# USB_C_Vertical_Breakout-PTH.net
KiCad netlist of a schematic drawn in EAGLE
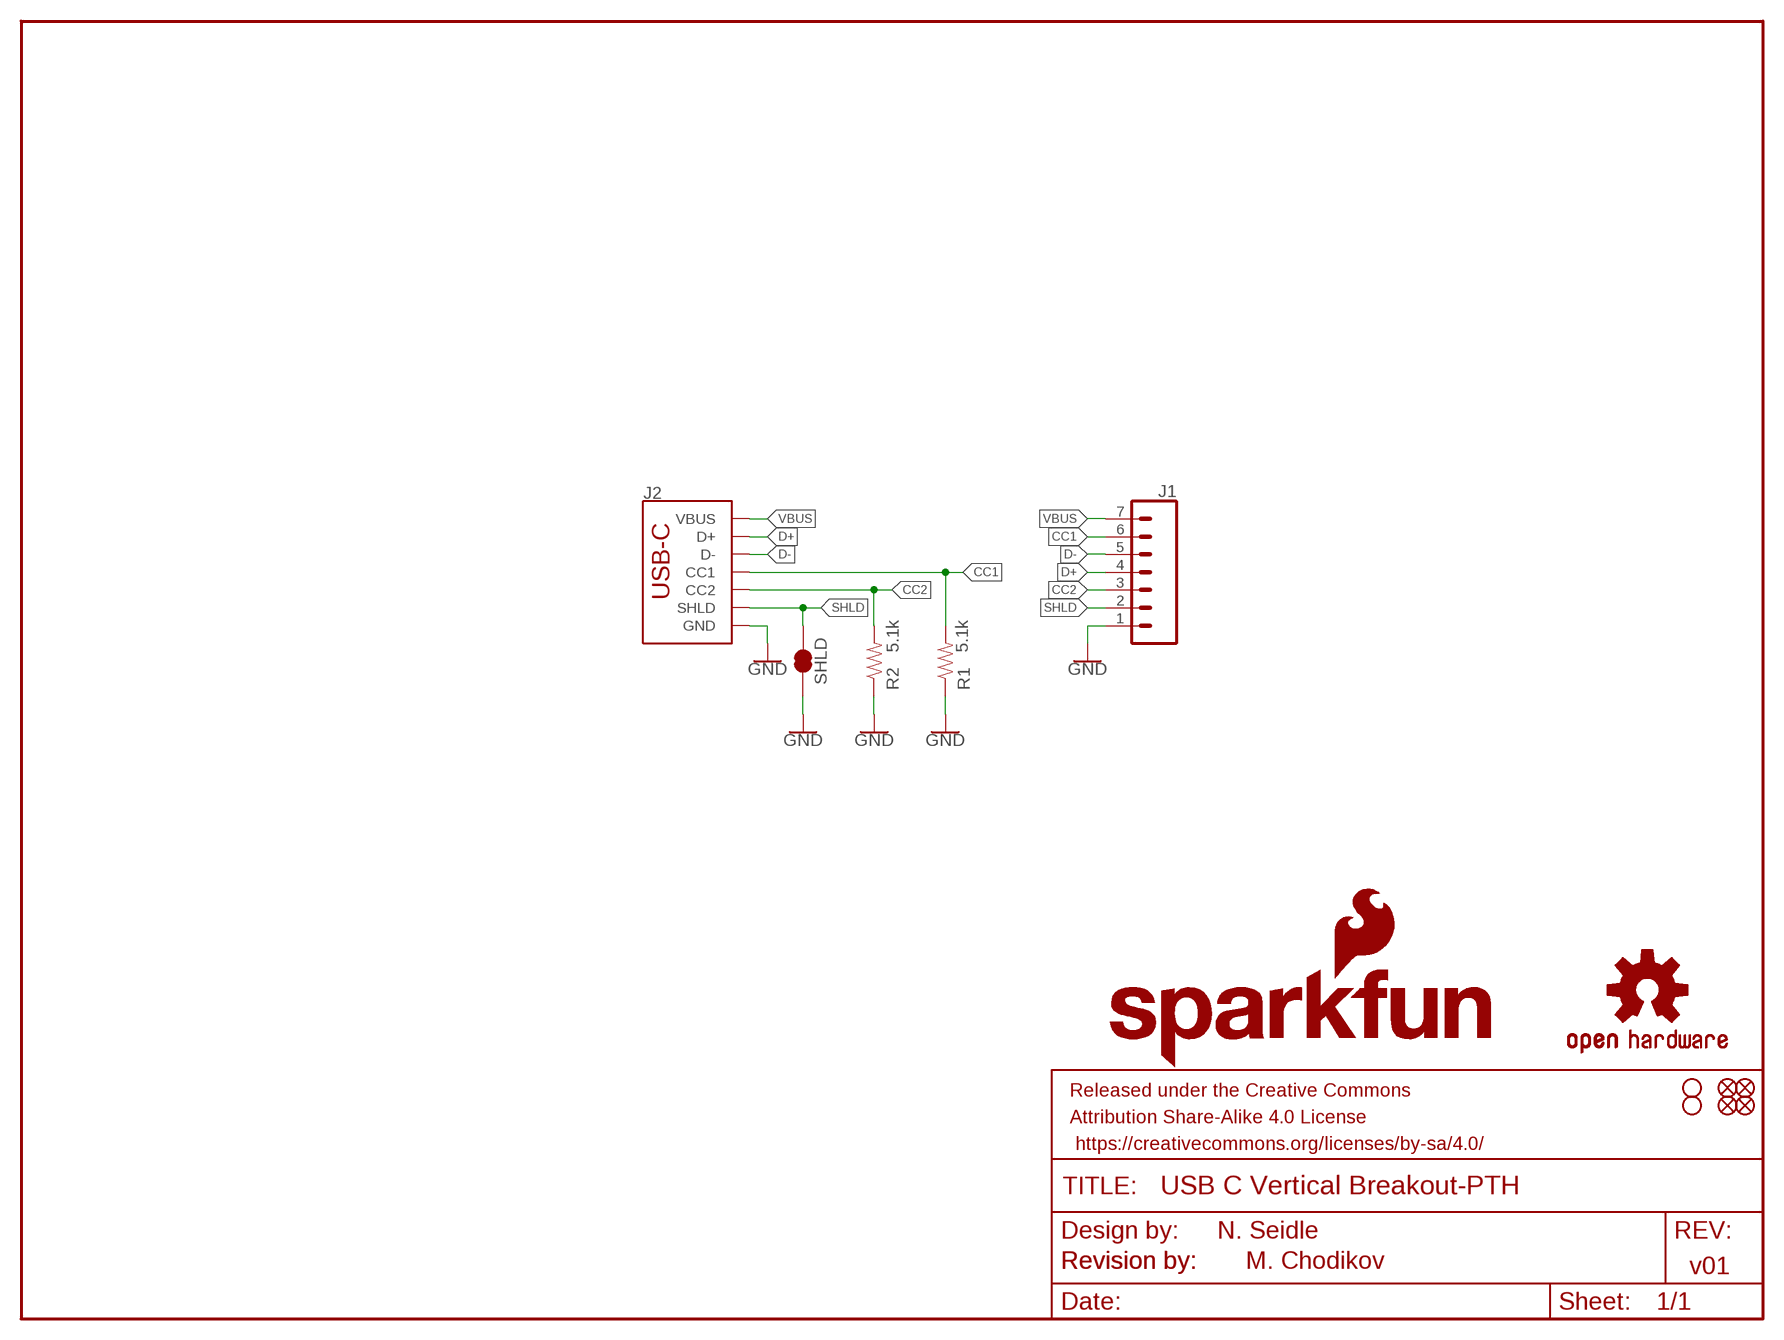
[diagram p0: schematic, sheet 1]

(export (version "E")
  (design (tool "Eeschema 10.0.6"))
  (components
    (comp (ref "FD1")
      (value "FIDUCIALUFIDUCIAL")
      (footprint "eagle-import:FIDUCIAL-MICRO")
      (libsource (lib "eagle-import") (part "FIDUCIALUFIDUCIAL"))
    )
    (comp (ref "FD2")
      (value "FIDUCIALUFIDUCIAL")
      (footprint "eagle-import:FIDUCIAL-MICRO")
      (libsource (lib "eagle-import") (part "FIDUCIALUFIDUCIAL"))
    )
    (comp (ref "FD3")
      (value "FIDUCIALUFIDUCIAL")
      (footprint "eagle-import:FIDUCIAL-MICRO")
      (libsource (lib "eagle-import") (part "FIDUCIALUFIDUCIAL"))
    )
    (comp (ref "FD4")
      (value "FIDUCIALUFIDUCIAL")
      (footprint "eagle-import:FIDUCIAL-MICRO")
      (libsource (lib "eagle-import") (part "FIDUCIALUFIDUCIAL"))
    )
    (comp (ref "FRAME2")
      (value "FRAME-LETTER")
      (footprint "eagle-import:CREATIVE_COMMONS")
      (libsource (lib "eagle-import") (part "FRAME-LETTER"))
    )
    (comp (ref "H1")
      (value "STAND-OFFTIGHT")
      (footprint "eagle-import:STAND-OFF-TIGHT")
      (libsource (lib "eagle-import") (part "STAND-OFFTIGHT"))
    )
    (comp (ref "H2")
      (value "STAND-OFFTIGHT")
      (footprint "eagle-import:STAND-OFF-TIGHT")
      (libsource (lib "eagle-import") (part "STAND-OFFTIGHT"))
    )
    (comp (ref "J1")
      (value "CONN_07NO_SILK")
      (footprint "eagle-import:1X07_NO_SILK")
      (libsource (lib "eagle-import") (part "CONN_07NO_SILK"))
    )
    (comp (ref "J2")
      (value "USB_C_2-LAYER-VERTICAL-PTH")
      (footprint "eagle-import:USB-C-8P-2LAYER-VERTICAL-PTH")
      (libsource (lib "eagle-import") (part "USB_C_2-LAYER-VERTICAL-PTH"))
    )
    (comp (ref "LOGO1")
      (value "SFE_LOGO_NAME_FLAMEBLANK")
      (footprint "eagle-import:BLANK")
      (libsource (lib "eagle-import") (part "SFE_LOGO_NAME_FLAMEBLANK"))
    )
    (comp (ref "LOGO2")
      (value "OSHW-LOGOMINI")
      (footprint "eagle-import:OSHW-LOGO-MINI")
      (libsource (lib "eagle-import") (part "OSHW-LOGOMINI"))
    )
    (comp (ref "LOGO3")
      (value "SFE_LOGO_FLAME.1_INCH")
      (footprint "eagle-import:SFE_LOGO_FLAME_.1")
      (libsource (lib "eagle-import") (part "SFE_LOGO_FLAME.1_INCH"))
    )
    (comp (ref "R1")
      (value "5.1k")
      (footprint "eagle-import:0603")
      (libsource (lib "eagle-import") (part "5.1KOHM5.1KOHM-0603-1/10W-1%"))
    )
    (comp (ref "R2")
      (value "5.1k")
      (footprint "eagle-import:0603")
      (libsource (lib "eagle-import") (part "5.1KOHM5.1KOHM-0603-1/10W-1%"))
    )
    (comp (ref "SHLD")
      (value "SHLD")
      (footprint "eagle-import:SMT-JUMPER_2_NC_TRACE_NO-SILK")
      (libsource (lib "eagle-import") (part "JUMPER-SMT_2_NC_TRACE_NO-SILK"))
    )
  )
  (nets
    (net (code "1") (name "CC1") (class "Default")
      (node (ref "J1") (pin "6") (pinfunction "6_6") (pintype "passive"))
      (node (ref "J2") (pin "A5") (pinfunction "CC1_A5") (pintype "bidirectional"))
      (node (ref "R1") (pin "2") (pinfunction "2_2") (pintype "passive"))
    )
    (net (code "2") (name "CC2") (class "Default")
      (node (ref "J1") (pin "3") (pinfunction "3_3") (pintype "passive"))
      (node (ref "J2") (pin "B5") (pinfunction "CC2_B5") (pintype "bidirectional"))
      (node (ref "R2") (pin "2") (pinfunction "2_2") (pintype "passive"))
    )
    (net (code "3") (name "D+") (class "Default")
      (node (ref "J1") (pin "4") (pinfunction "4_4") (pintype "passive"))
      (node (ref "J2") (pin "A6") (pinfunction "D+_A6") (pintype "bidirectional"))
      (node (ref "J2") (pin "B6") (pinfunction "D+_B6") (pintype "bidirectional"))
    )
    (net (code "4") (name "D-") (class "Default")
      (node (ref "J1") (pin "5") (pinfunction "5_5") (pintype "passive"))
      (node (ref "J2") (pin "A7") (pinfunction "D-_A7") (pintype "bidirectional"))
      (node (ref "J2") (pin "B7") (pinfunction "D-_B7") (pintype "bidirectional"))
    )
    (net (code "5") (name "GND") (class "Default")
      (node (ref "J1") (pin "1") (pinfunction "1_1") (pintype "passive"))
      (node (ref "J2") (pin "A1") (pinfunction "GND_A1") (pintype "bidirectional"))
      (node (ref "J2") (pin "A12") (pinfunction "GND_A12") (pintype "bidirectional"))
      (node (ref "J2") (pin "B1") (pinfunction "GND_B1") (pintype "bidirectional"))
      (node (ref "J2") (pin "B12") (pinfunction "GND_B12") (pintype "bidirectional"))
      (node (ref "R1") (pin "1") (pinfunction "1_1") (pintype "passive"))
      (node (ref "R2") (pin "1") (pinfunction "1_1") (pintype "passive"))
      (node (ref "SHLD") (pin "1") (pinfunction "1_1") (pintype "passive"))
    )
    (net (code "6") (name "SHLD") (class "Default")
      (node (ref "J1") (pin "2") (pinfunction "2_2") (pintype "passive"))
      (node (ref "J2") (pin "SHLD1") (pinfunction "SHLD_SHLD1") (pintype "bidirectional"))
      (node (ref "J2") (pin "SHLD2") (pinfunction "SHLD_SHLD2") (pintype "bidirectional"))
      (node (ref "J2") (pin "SHLD3") (pinfunction "SHLD_SHLD3") (pintype "bidirectional"))
      (node (ref "J2") (pin "SHLD4") (pinfunction "SHLD_SHLD4") (pintype "bidirectional"))
      (node (ref "SHLD") (pin "2") (pinfunction "2_2") (pintype "passive"))
    )
    (net (code "7") (name "VBUS") (class "Default")
      (node (ref "J1") (pin "7") (pinfunction "7_7") (pintype "passive"))
      (node (ref "J2") (pin "A4") (pinfunction "VBUS_A4") (pintype "bidirectional"))
      (node (ref "J2") (pin "A9") (pinfunction "VBUS_A9") (pintype "bidirectional"))
      (node (ref "J2") (pin "B4") (pinfunction "VBUS_B4") (pintype "bidirectional"))
      (node (ref "J2") (pin "B9") (pinfunction "VBUS_B9") (pintype "bidirectional"))
    )
  )
)
